# LCD_Display.net
KiCad netlist of a schematic drawn in Altium Designer
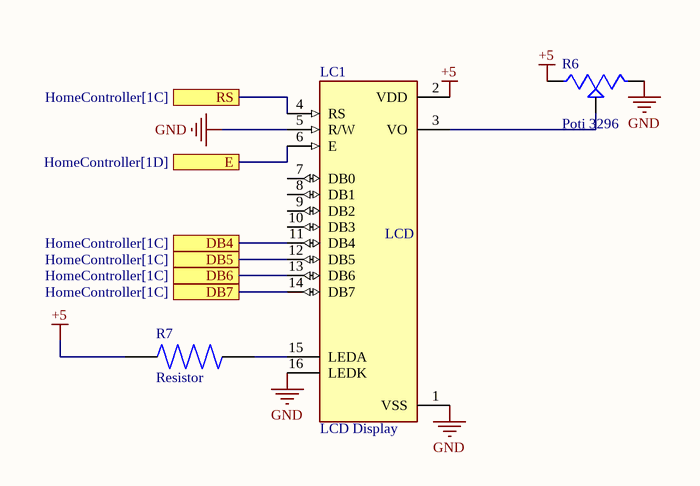
[diagram p0: LCD Display.SchDoc]

(export (version "E")
  (design (tool "Eeschema 10.0.6"))
  (components
    (comp (ref "LC1")
      (value "LCD Display")
      (footprint "LCD Display-Footprint-1")
      (description "16x2 LCD Display")
      (libsource (lib "Tobias") (part "LCD Display-Symbol-1"))
    )
    (comp (ref "R6")
      (value "Poti 3296")
      (footprint "Poti 3296-Footprint-1")
      (description "Generic Potentiometer")
      (libsource (lib "Tobias") (part "Poti 3296-Symbol-1"))
    )
    (comp (ref "R7")
      (value "Resistor")
      (footprint "Resistor-Footprint-1")
      (description "Generic Resistor")
      (libsource (lib "Tobias") (part "Resistor-Symbol-1"))
    )
  )
  (nets
    (net (code "1") (name "+5") (class "Default")
      (node (ref "LC1") (pin "2") (pinfunction "VDD_2") (pintype "power_in"))
      (node (ref "R6") (pin "1") (pinfunction "CCW_1") (pintype "passive"))
      (node (ref "R7") (pin "1") (pinfunction "1_1") (pintype "passive"))
    )
    (net (code "2") (name "/DB4") (class "Default")
      (node (ref "LC1") (pin "11") (pinfunction "DB4_11") (pintype "bidirectional"))
    )
    (net (code "3") (name "/DB5") (class "Default")
      (node (ref "LC1") (pin "12") (pinfunction "DB5_12") (pintype "bidirectional"))
    )
    (net (code "4") (name "/DB6") (class "Default")
      (node (ref "LC1") (pin "13") (pinfunction "DB6_13") (pintype "bidirectional"))
    )
    (net (code "5") (name "/DB7") (class "Default")
      (node (ref "LC1") (pin "14") (pinfunction "DB7_14") (pintype "bidirectional"))
    )
    (net (code "6") (name "/E") (class "Default")
      (node (ref "LC1") (pin "6") (pinfunction "E_6") (pintype "input"))
    )
    (net (code "7") (name "/RS") (class "Default")
      (node (ref "LC1") (pin "4") (pinfunction "RS_4") (pintype "input"))
    )
    (net (code "8") (name "GND") (class "Default")
      (node (ref "LC1") (pin "1") (pinfunction "VSS_1") (pintype "power_in"))
      (node (ref "LC1") (pin "16") (pinfunction "LEDK_16") (pintype "passive"))
      (node (ref "LC1") (pin "5") (pinfunction "R/W_5") (pintype "input"))
      (node (ref "R6") (pin "3") (pinfunction "CW_3") (pintype "passive"))
    )
    (net (code "9") (name "Net-(LC1-LEDA)") (class "Default")
      (node (ref "LC1") (pin "15") (pinfunction "LEDA_15") (pintype "passive"))
      (node (ref "R7") (pin "2") (pinfunction "2_2") (pintype "passive"))
    )
    (net (code "10") (name "Net-(LC1-VO)") (class "Default")
      (node (ref "LC1") (pin "3") (pinfunction "VO_3") (pintype "passive"))
      (node (ref "R6") (pin "2") (pinfunction "WIPER_2") (pintype "passive"))
    )
    (net (code "11") (name "unconnected-(LC1-DB0-Pad7)") (class "Default")
      (node (ref "LC1") (pin "7") (pinfunction "DB0_7") (pintype "bidirectional"))
    )
    (net (code "12") (name "unconnected-(LC1-DB1-Pad8)") (class "Default")
      (node (ref "LC1") (pin "8") (pinfunction "DB1_8") (pintype "bidirectional"))
    )
    (net (code "13") (name "unconnected-(LC1-DB2-Pad9)") (class "Default")
      (node (ref "LC1") (pin "9") (pinfunction "DB2_9") (pintype "bidirectional"))
    )
    (net (code "14") (name "unconnected-(LC1-DB3-Pad10)") (class "Default")
      (node (ref "LC1") (pin "10") (pinfunction "DB3_10") (pintype "bidirectional"))
    )
  )
)
